# DasAltimeter_square_v0_1.net
KiCad netlist of a schematic drawn in EAGLE
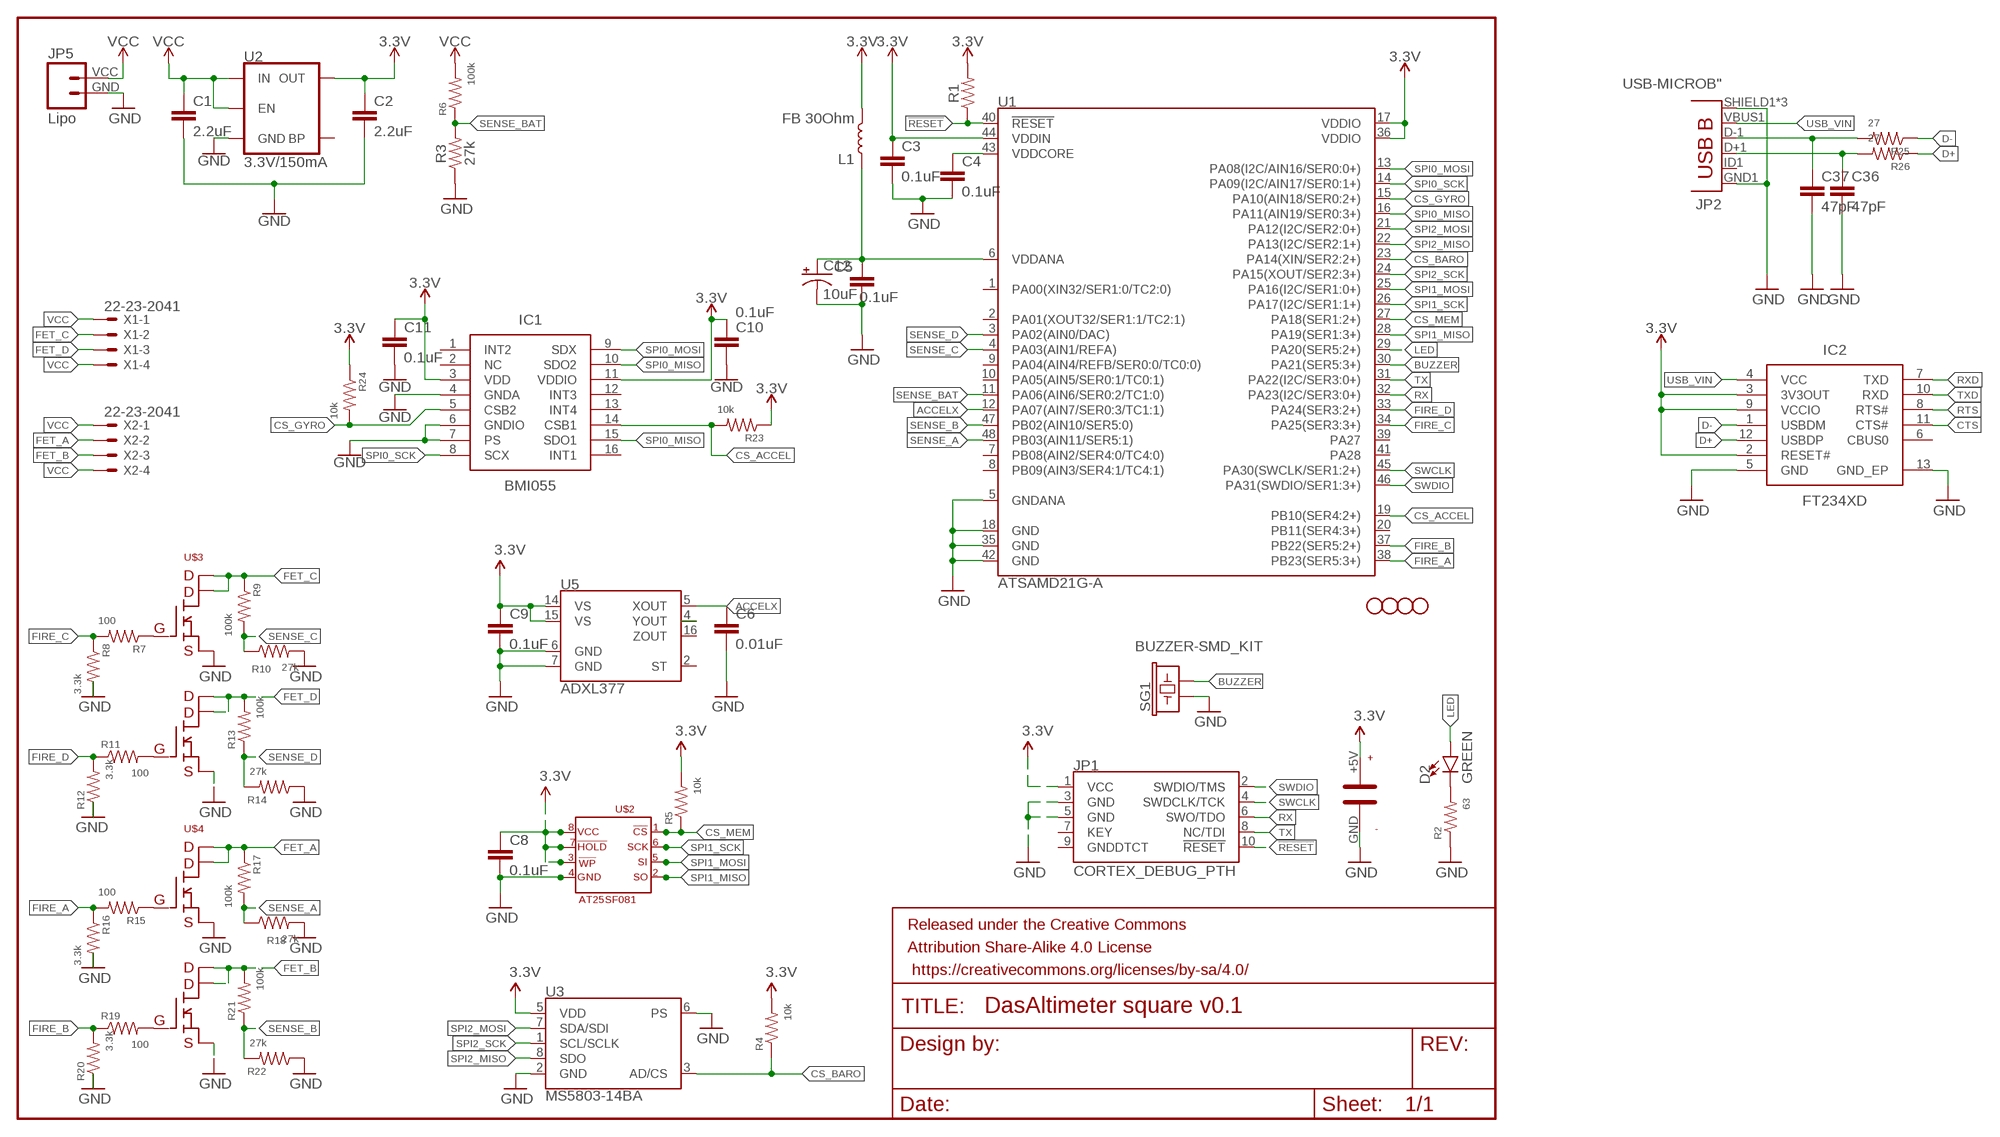
[diagram p0: schematic, sheet 1]

(export (version "E")
  (design (tool "Eeschema 10.0.6"))
  (components
    (comp (ref "C1")
      (value "2.2uF")
      (footprint "eagle-import:0603")
      (libsource (lib "eagle-import") (part "2.2UF-0603-10V-20%"))
    )
    (comp (ref "C2")
      (value "2.2uF")
      (footprint "eagle-import:0603")
      (libsource (lib "eagle-import") (part "2.2UF-0603-10V-20%"))
    )
    (comp (ref "C3")
      (value "0.1uF")
      (footprint "eagle-import:0402")
      (libsource (lib "eagle-import") (part "0.1UF-0402-16V-10%"))
    )
    (comp (ref "C4")
      (value "0.1uF")
      (footprint "eagle-import:0402")
      (libsource (lib "eagle-import") (part "0.1UF-0402-16V-10%"))
    )
    (comp (ref "C5")
      (value "0.1uF")
      (footprint "eagle-import:0402")
      (libsource (lib "eagle-import") (part "0.1UF-0402-16V-10%"))
    )
    (comp (ref "C6")
      (value "0.01uF")
      (footprint "eagle-import:0402")
      (libsource (lib "eagle-import") (part "0.1UF-0402-16V-10%"))
    )
    (comp (ref "C8")
      (value "0.1uF")
      (footprint "eagle-import:0402")
      (libsource (lib "eagle-import") (part "0.1UF-0402-16V-10%"))
    )
    (comp (ref "C9")
      (value "0.1uF")
      (footprint "eagle-import:0402")
      (libsource (lib "eagle-import") (part "0.1UF-0402-16V-10%"))
    )
    (comp (ref "C10")
      (value "0.1uF")
      (footprint "eagle-import:0402")
      (libsource (lib "eagle-import") (part "0.1UF-0402-16V-10%"))
    )
    (comp (ref "C11")
      (value "0.1uF")
      (footprint "eagle-import:0402")
      (libsource (lib "eagle-import") (part "0.1UF-0402-16V-10%"))
    )
    (comp (ref "C12")
      (value "10uF")
      (footprint "eagle-import:0603-POLAR")
      (libsource (lib "eagle-import") (part "10UF-POLAR-0603-6.3V-20%(TANT)"))
    )
    (comp (ref "C36")
      (value "47pF")
      (footprint "eagle-import:0402")
      (libsource (lib "eagle-import") (part "0.1UF-0402-16V-10%"))
    )
    (comp (ref "C37")
      (value "47pF")
      (footprint "eagle-import:0402")
      (libsource (lib "eagle-import") (part "0.1UF-0402-16V-10%"))
    )
    (comp (ref "D2")
      (value "GREEN")
      (footprint "eagle-import:LED-1206")
      (libsource (lib "eagle-import") (part "LED-GREEN1206"))
    )
    (comp (ref "FRAME1")
      (value "FRAME-LETTERNO_PACKAGE")
      (footprint "eagle-import:DUMMY")
      (fields (field (name "DESIGNER") "Nobody"))
      (libsource (lib "eagle-import") (part "FRAME-LETTERNO_PACKAGE"))
    )
    (comp (ref "H1")
      (value "STAND-OFFTIGHT")
      (footprint "eagle-import:STAND-OFF-TIGHT")
      (libsource (lib "eagle-import") (part "STAND-OFFTIGHT"))
    )
    (comp (ref "H2")
      (value "STAND-OFFTIGHT")
      (footprint "eagle-import:STAND-OFF-TIGHT")
      (libsource (lib "eagle-import") (part "STAND-OFFTIGHT"))
    )
    (comp (ref "H3")
      (value "STAND-OFFTIGHT")
      (footprint "eagle-import:STAND-OFF-TIGHT")
      (libsource (lib "eagle-import") (part "STAND-OFFTIGHT"))
    )
    (comp (ref "H4")
      (value "STAND-OFFTIGHT")
      (footprint "eagle-import:STAND-OFF-TIGHT")
      (libsource (lib "eagle-import") (part "STAND-OFFTIGHT"))
    )
    (comp (ref "IC1")
      (value "BMI055")
      (footprint "eagle-import:BMI055")
      (libsource (lib "eagle-import") (part "BMI055"))
    )
    (comp (ref "IC2")
      (value "FT234XD")
      (footprint "eagle-import:SON45P300X300X80-13N")
      (fields (field (name "MANUFACTURER_PART_NUMBER") "ft234xd"))
      (libsource (lib "eagle-import") (part "FT234XD"))
    )
    (comp (ref "JP1")
      (value "CORTEX_DEBUG_PTH")
      (footprint "eagle-import:2X5-PTH-1.27MM")
      (libsource (lib "eagle-import") (part "CORTEX_DEBUG_PTH"))
    )
    (comp (ref "JP2")
      (value "USB-MICROB\"")
      (footprint "eagle-import:USB-B-MICRO-SMD_V03")
      (libsource (lib "eagle-import") (part "USB-MICROB{dblquote}"))
    )
    (comp (ref "JP5")
      (value "Lipo")
      (footprint "eagle-import:JST-2-SMD-VERT")
      (libsource (lib "eagle-import") (part "M024UCON-15767"))
    )
    (comp (ref "L1")
      (value "FB 30Ohm")
      (footprint "eagle-import:0603")
      (libsource (lib "eagle-import") (part "INDUCTOR-0603-33NH"))
    )
    (comp (ref "R1")
      (value "RESISTOR0402")
      (footprint "eagle-import:0402")
      (libsource (lib "eagle-import") (part "RESISTOR0402"))
    )
    (comp (ref "R2")
      (value "63")
      (footprint "eagle-import:0402")
      (libsource (lib "eagle-import") (part "RESISTOR0402"))
    )
    (comp (ref "R3")
      (value "27k")
      (footprint "eagle-import:0402")
      (libsource (lib "eagle-import") (part "RESISTOR0402"))
    )
    (comp (ref "R4")
      (value "10k")
      (footprint "eagle-import:0402")
      (libsource (lib "eagle-import") (part "RESISTOR0402"))
    )
    (comp (ref "R5")
      (value "10k")
      (footprint "eagle-import:0402")
      (libsource (lib "eagle-import") (part "RESISTOR0402"))
    )
    (comp (ref "R6")
      (value "100k")
      (footprint "eagle-import:0402")
      (libsource (lib "eagle-import") (part "RESISTOR0402"))
    )
    (comp (ref "R7")
      (value "100")
      (footprint "eagle-import:0402")
      (libsource (lib "eagle-import") (part "RESISTOR0402"))
    )
    (comp (ref "R8")
      (value "3.3k")
      (footprint "eagle-import:0402")
      (libsource (lib "eagle-import") (part "RESISTOR0402"))
    )
    (comp (ref "R9")
      (value "100k")
      (footprint "eagle-import:0402")
      (libsource (lib "eagle-import") (part "RESISTOR0402"))
    )
    (comp (ref "R10")
      (value "27k")
      (footprint "eagle-import:0402")
      (libsource (lib "eagle-import") (part "RESISTOR0402"))
    )
    (comp (ref "R11")
      (value "100")
      (footprint "eagle-import:0402")
      (libsource (lib "eagle-import") (part "RESISTOR0402"))
    )
    (comp (ref "R12")
      (value "3.3k")
      (footprint "eagle-import:0402")
      (libsource (lib "eagle-import") (part "RESISTOR0402"))
    )
    (comp (ref "R13")
      (value "100k")
      (footprint "eagle-import:0402")
      (libsource (lib "eagle-import") (part "RESISTOR0402"))
    )
    (comp (ref "R14")
      (value "27k")
      (footprint "eagle-import:0402")
      (libsource (lib "eagle-import") (part "RESISTOR0402"))
    )
    (comp (ref "R15")
      (value "100")
      (footprint "eagle-import:0402")
      (libsource (lib "eagle-import") (part "RESISTOR0402"))
    )
    (comp (ref "R16")
      (value "3.3k")
      (footprint "eagle-import:0402")
      (libsource (lib "eagle-import") (part "RESISTOR0402"))
    )
    (comp (ref "R17")
      (value "100k")
      (footprint "eagle-import:0402")
      (libsource (lib "eagle-import") (part "RESISTOR0402"))
    )
    (comp (ref "R18")
      (value "27k")
      (footprint "eagle-import:0402")
      (libsource (lib "eagle-import") (part "RESISTOR0402"))
    )
    (comp (ref "R19")
      (value "100")
      (footprint "eagle-import:0402")
      (libsource (lib "eagle-import") (part "RESISTOR0402"))
    )
    (comp (ref "R20")
      (value "3.3k")
      (footprint "eagle-import:0402")
      (libsource (lib "eagle-import") (part "RESISTOR0402"))
    )
    (comp (ref "R21")
      (value "100k")
      (footprint "eagle-import:0402")
      (libsource (lib "eagle-import") (part "RESISTOR0402"))
    )
    (comp (ref "R22")
      (value "27k")
      (footprint "eagle-import:0402")
      (libsource (lib "eagle-import") (part "RESISTOR0402"))
    )
    (comp (ref "R23")
      (value "10k")
      (footprint "eagle-import:0402")
      (libsource (lib "eagle-import") (part "RESISTOR0402"))
    )
    (comp (ref "R24")
      (value "10k")
      (footprint "eagle-import:0402")
      (libsource (lib "eagle-import") (part "RESISTOR0402"))
    )
    (comp (ref "R25")
      (value "27")
      (footprint "eagle-import:0402")
      (libsource (lib "eagle-import") (part "RESISTOR0402"))
    )
    (comp (ref "R26")
      (value "27")
      (footprint "eagle-import:0402")
      (libsource (lib "eagle-import") (part "RESISTOR0402"))
    )
    (comp (ref "SG1")
      (value "BUZZER-SMD_KIT")
      (footprint "eagle-import:BUZZER-CCV-KIT")
      (libsource (lib "eagle-import") (part "BUZZER-SMD_KIT"))
    )
    (comp (ref "U$1")
      (value "PB-5R0H104-R")
      (footprint "eagle-import:PB-5R0H104-R")
      (libsource (lib "eagle-import") (part "PB-5R0H104-R"))
    )
    (comp (ref "U$2")
      (value "AT25SF081")
      (footprint "eagle-import:AT25SF081")
      (libsource (lib "eagle-import") (part "AT25SF081"))
    )
    (comp (ref "U$3")
      (value "SI7232DN")
      (footprint "eagle-import:SI7232DN")
      (libsource (lib "eagle-import") (part "SI7232DN"))
    )
    (comp (ref "U$4")
      (value "SI7232DN")
      (footprint "eagle-import:SI7232DN")
      (libsource (lib "eagle-import") (part "SI7232DN"))
    )
    (comp (ref "U1")
      (value "ATSAMD21G-A")
      (footprint "eagle-import:TQFP-48")
      (libsource (lib "eagle-import") (part "ATSAMD21G-A"))
    )
    (comp (ref "U2")
      (value "3.3V/150mA")
      (footprint "eagle-import:SOT23-5")
      (libsource (lib "eagle-import") (part "V_REG_MIC52053.3V"))
    )
    (comp (ref "U3")
      (value "MS5803-14BA")
      (footprint "eagle-import:MS5803")
      (libsource (lib "eagle-import") (part "MS5803-14BA"))
    )
    (comp (ref "U5")
      (value "ADXL377")
      (footprint "eagle-import:LFCSP-16-3X3")
      (libsource (lib "eagle-import") (part "ADXL377"))
    )
    (comp (ref "X1")
      (value "22-23-2041")
      (footprint "eagle-import:22-23-2041")
      (fields (field (name "MF") "MOLEX"))
      (libsource (lib "eagle-import") (part "22-23-2041"))
    )
    (comp (ref "X2")
      (value "22-23-2041")
      (footprint "eagle-import:22-23-2041")
      (fields (field (name "MF") "MOLEX"))
      (libsource (lib "eagle-import") (part "22-23-2041"))
    )
  )
  (nets
    (net (code "1") (name "/~{RESET}") (class "Default")
      (node (ref "JP1") (pin "10") (pinfunction "~{RESET}_10") (pintype "bidirectional"))
      (node (ref "R1") (pin "1") (pinfunction "1_1") (pintype "passive"))
      (node (ref "U1") (pin "40") (pinfunction "~{RESET}_40") (pintype "bidirectional"))
    )
    (net (code "2") (name "3.3V") (class "Default")
      (node (ref "C10") (pin "1") (pinfunction "1_1") (pintype "passive"))
      (node (ref "C11") (pin "1") (pinfunction "1_1") (pintype "passive"))
      (node (ref "C2") (pin "1") (pinfunction "1_1") (pintype "passive"))
      (node (ref "C3") (pin "1") (pinfunction "1_1") (pintype "passive"))
      (node (ref "C8") (pin "1") (pinfunction "1_1") (pintype "passive"))
      (node (ref "C9") (pin "1") (pinfunction "1_1") (pintype "passive"))
      (node (ref "IC1") (pin "11") (pinfunction "VDDIO_11") (pintype "passive"))
      (node (ref "IC1") (pin "3") (pinfunction "VDD_3") (pintype "passive"))
      (node (ref "IC2") (pin "2") (pinfunction "RESET#_2") (pintype "passive"))
      (node (ref "IC2") (pin "3") (pinfunction "3V3OUT_3") (pintype "output"))
      (node (ref "IC2") (pin "9") (pinfunction "VCCIO_9") (pintype "power_in"))
      (node (ref "JP1") (pin "1") (pinfunction "VCC_1") (pintype "bidirectional"))
      (node (ref "L1") (pin "2") (pinfunction "2_2") (pintype "passive"))
      (node (ref "R1") (pin "2") (pinfunction "2_2") (pintype "passive"))
      (node (ref "R23") (pin "1") (pinfunction "1_1") (pintype "passive"))
      (node (ref "R24") (pin "1") (pinfunction "1_1") (pintype "passive"))
      (node (ref "R4") (pin "2") (pinfunction "2_2") (pintype "passive"))
      (node (ref "R5") (pin "2") (pinfunction "2_2") (pintype "passive"))
      (node (ref "U$1") (pin "+5V") (pinfunction "+5V_+5V") (pintype "bidirectional"))
      (node (ref "U$2") (pin "!HOLD") (pinfunction "~{HOLD}_!HOLD") (pintype "bidirectional"))
      (node (ref "U$2") (pin "!WP") (pinfunction "~{WP}_!WP") (pintype "bidirectional"))
      (node (ref "U$2") (pin "VCC") (pinfunction "VCC_VCC") (pintype "bidirectional"))
      (node (ref "U1") (pin "17") (pinfunction "VDDIO_17") (pintype "bidirectional"))
      (node (ref "U1") (pin "36") (pinfunction "VDDIO_36") (pintype "bidirectional"))
      (node (ref "U1") (pin "44") (pinfunction "VDDIN_44") (pintype "bidirectional"))
      (node (ref "U2") (pin "5") (pinfunction "OUT_5") (pintype "passive"))
      (node (ref "U3") (pin "5") (pinfunction "VDD_5") (pintype "bidirectional"))
      (node (ref "U5") (pin "14") (pinfunction "VS_14") (pintype "bidirectional"))
      (node (ref "U5") (pin "15") (pinfunction "VS_15") (pintype "bidirectional"))
    )
    (net (code "3") (name "ACCELX") (class "Default")
      (node (ref "C6") (pin "1") (pinfunction "1_1") (pintype "passive"))
      (node (ref "U1") (pin "12") (pinfunction "PA07(AIN7/SER0:3/TC1:1)_12") (pintype "bidirectional"))
      (node (ref "U5") (pin "5") (pinfunction "XOUT_5") (pintype "bidirectional"))
    )
    (net (code "4") (name "BUZZER") (class "Default")
      (node (ref "SG1") (pin "-") (pinfunction "2_-") (pintype "passive"))
      (node (ref "U1") (pin "30") (pinfunction "PA21(SER5:3+)_30") (pintype "bidirectional"))
    )
    (net (code "5") (name "CS_ACCEL") (class "Default")
      (node (ref "IC1") (pin "14") (pinfunction "CSB1_14") (pintype "passive"))
      (node (ref "R23") (pin "2") (pinfunction "2_2") (pintype "passive"))
      (node (ref "U1") (pin "19") (pinfunction "PB10(SER4:2+)_19") (pintype "bidirectional"))
    )
    (net (code "6") (name "CS_BARO") (class "Default")
      (node (ref "R4") (pin "1") (pinfunction "1_1") (pintype "passive"))
      (node (ref "U1") (pin "23") (pinfunction "PA14(XIN/SER2:2+)_23") (pintype "bidirectional"))
      (node (ref "U3") (pin "3") (pinfunction "AD/CS_3") (pintype "bidirectional"))
    )
    (net (code "7") (name "CS_GYRO") (class "Default")
      (node (ref "IC1") (pin "5") (pinfunction "CSB2_5") (pintype "passive"))
      (node (ref "R24") (pin "2") (pinfunction "2_2") (pintype "passive"))
      (node (ref "U1") (pin "15") (pinfunction "PA10(AIN18/SER0:2+)_15") (pintype "bidirectional"))
    )
    (net (code "8") (name "CS_MEM") (class "Default")
      (node (ref "R5") (pin "1") (pinfunction "1_1") (pintype "passive"))
      (node (ref "U$2") (pin "!CS") (pinfunction "~{CS}_!CS") (pintype "bidirectional"))
      (node (ref "U1") (pin "27") (pinfunction "PA18(SER1:2+)_27") (pintype "bidirectional"))
    )
    (net (code "9") (name "CTS") (class "Default")
      (node (ref "IC2") (pin "11") (pinfunction "CTS#_11") (pintype "passive"))
    )
    (net (code "10") (name "D+") (class "Default")
      (node (ref "IC2") (pin "12") (pinfunction "USBDP_12") (pintype "passive"))
      (node (ref "R26") (pin "1") (pinfunction "1_1") (pintype "passive"))
    )
    (net (code "11") (name "D-") (class "Default")
      (node (ref "IC2") (pin "1") (pinfunction "USBDM_1") (pintype "passive"))
      (node (ref "R25") (pin "1") (pinfunction "1_1") (pintype "passive"))
    )
    (net (code "12") (name "FET_A") (class "Default")
      (node (ref "R17") (pin "1") (pinfunction "1_1") (pintype "passive"))
      (node (ref "U$4") (pin "7") (pinfunction "PIN7_7") (pintype "bidirectional"))
      (node (ref "U$4") (pin "8") (pinfunction "PIN8_8") (pintype "bidirectional"))
      (node (ref "U$4") (pin "9") (pinfunction "PIN8_9") (pintype "bidirectional"))
      (node (ref "X2") (pin "2") (pinfunction "S_2") (pintype "passive"))
    )
    (net (code "13") (name "FET_B") (class "Default")
      (node (ref "R21") (pin "2") (pinfunction "2_2") (pintype "passive"))
      (node (ref "U$4") (pin "10") (pinfunction "PIN5_10") (pintype "bidirectional"))
      (node (ref "U$4") (pin "5") (pinfunction "PIN5_5") (pintype "bidirectional"))
      (node (ref "U$4") (pin "6") (pinfunction "PIN6_6") (pintype "bidirectional"))
      (node (ref "X2") (pin "3") (pinfunction "S_3") (pintype "passive"))
    )
    (net (code "14") (name "FET_C") (class "Default")
      (node (ref "R9") (pin "1") (pinfunction "1_1") (pintype "passive"))
      (node (ref "U$3") (pin "7") (pinfunction "PIN7_7") (pintype "bidirectional"))
      (node (ref "U$3") (pin "8") (pinfunction "PIN8_8") (pintype "bidirectional"))
      (node (ref "U$3") (pin "9") (pinfunction "PIN8_9") (pintype "bidirectional"))
      (node (ref "X1") (pin "2") (pinfunction "S_2") (pintype "passive"))
    )
    (net (code "15") (name "FET_D") (class "Default")
      (node (ref "R13") (pin "2") (pinfunction "2_2") (pintype "passive"))
      (node (ref "U$3") (pin "10") (pinfunction "PIN5_10") (pintype "bidirectional"))
      (node (ref "U$3") (pin "5") (pinfunction "PIN5_5") (pintype "bidirectional"))
      (node (ref "U$3") (pin "6") (pinfunction "PIN6_6") (pintype "bidirectional"))
      (node (ref "X1") (pin "3") (pinfunction "S_3") (pintype "passive"))
    )
    (net (code "16") (name "FIRE_A") (class "Default")
      (node (ref "R15") (pin "2") (pinfunction "2_2") (pintype "passive"))
      (node (ref "R16") (pin "1") (pinfunction "1_1") (pintype "passive"))
      (node (ref "U1") (pin "38") (pinfunction "PB23(SER5:3+)_38") (pintype "bidirectional"))
    )
    (net (code "17") (name "FIRE_B") (class "Default")
      (node (ref "R19") (pin "1") (pinfunction "1_1") (pintype "passive"))
      (node (ref "R20") (pin "2") (pinfunction "2_2") (pintype "passive"))
      (node (ref "U1") (pin "37") (pinfunction "PB22(SER5:2+)_37") (pintype "bidirectional"))
    )
    (net (code "18") (name "FIRE_C") (class "Default")
      (node (ref "R7") (pin "2") (pinfunction "2_2") (pintype "passive"))
      (node (ref "R8") (pin "1") (pinfunction "1_1") (pintype "passive"))
      (node (ref "U1") (pin "34") (pinfunction "PA25(SER3:3+)_34") (pintype "bidirectional"))
    )
    (net (code "19") (name "FIRE_D") (class "Default")
      (node (ref "R11") (pin "1") (pinfunction "1_1") (pintype "passive"))
      (node (ref "R12") (pin "2") (pinfunction "2_2") (pintype "passive"))
      (node (ref "U1") (pin "33") (pinfunction "PA24(SER3:2+)_33") (pintype "bidirectional"))
    )
    (net (code "20") (name "GND") (class "Default")
      (node (ref "C1") (pin "2") (pinfunction "2_2") (pintype "passive"))
      (node (ref "C10") (pin "2") (pinfunction "2_2") (pintype "passive"))
      (node (ref "C11") (pin "2") (pinfunction "2_2") (pintype "passive"))
      (node (ref "C12") (pin "-") (pinfunction "-_-") (pintype "passive"))
      (node (ref "C2") (pin "2") (pinfunction "2_2") (pintype "passive"))
      (node (ref "C3") (pin "2") (pinfunction "2_2") (pintype "passive"))
      (node (ref "C36") (pin "2") (pinfunction "2_2") (pintype "passive"))
      (node (ref "C37") (pin "2") (pinfunction "2_2") (pintype "passive"))
      (node (ref "C4") (pin "2") (pinfunction "2_2") (pintype "passive"))
      (node (ref "C5") (pin "2") (pinfunction "2_2") (pintype "passive"))
      (node (ref "C6") (pin "2") (pinfunction "2_2") (pintype "passive"))
      (node (ref "C8") (pin "2") (pinfunction "2_2") (pintype "passive"))
      (node (ref "C9") (pin "2") (pinfunction "2_2") (pintype "passive"))
      (node (ref "IC1") (pin "4") (pinfunction "GNDA_4") (pintype "passive"))
      (node (ref "IC1") (pin "6") (pinfunction "GNDIO_6") (pintype "passive"))
      (node (ref "IC1") (pin "7") (pinfunction "PS_7") (pintype "passive"))
      (node (ref "IC2") (pin "13") (pinfunction "GND_EP_13") (pintype "power_in"))
      (node (ref "IC2") (pin "5") (pinfunction "GND_5") (pintype "power_in"))
      (node (ref "JP1") (pin "3") (pinfunction "GND_3") (pintype "bidirectional"))
      (node (ref "JP1") (pin "5") (pinfunction "GND_5") (pintype "bidirectional"))
      (node (ref "JP2") (pin "GND1") (pinfunction "GND_GND1") (pintype "bidirectional"))
      (node (ref "JP2") (pin "SHIELD1") (pinfunction "SHIELD_SHIELD1") (pintype "bidirectional"))
      (node (ref "JP2") (pin "SHIELD2") (pinfunction "SHIELD_SHIELD2") (pintype "bidirectional"))
      (node (ref "JP2") (pin "SHIELD3") (pinfunction "SHIELD_SHIELD3") (pintype "bidirectional"))
      (node (ref "JP5") (pin "GND") (pinfunction "1_GND") (pintype "passive"))
      (node (ref "R10") (pin "2") (pinfunction "2_2") (pintype "passive"))
      (node (ref "R12") (pin "1") (pinfunction "1_1") (pintype "passive"))
      (node (ref "R14") (pin "1") (pinfunction "1_1") (pintype "passive"))
      (node (ref "R16") (pin "2") (pinfunction "2_2") (pintype "passive"))
      (node (ref "R18") (pin "2") (pinfunction "2_2") (pintype "passive"))
      (node (ref "R2") (pin "1") (pinfunction "1_1") (pintype "passive"))
      (node (ref "R20") (pin "1") (pinfunction "1_1") (pintype "passive"))
      (node (ref "R22") (pin "1") (pinfunction "1_1") (pintype "passive"))
      (node (ref "R3") (pin "1") (pinfunction "1_1") (pintype "passive"))
      (node (ref "R8") (pin "2") (pinfunction "2_2") (pintype "passive"))
      (node (ref "SG1") (pin "+") (pinfunction "1_+") (pintype "passive"))
      (node (ref "U$1") (pin "GND") (pinfunction "GND_GND") (pintype "bidirectional"))
      (node (ref "U$2") (pin "GND") (pinfunction "GND_GND") (pintype "bidirectional"))
      (node (ref "U$3") (pin "1") (pinfunction "PIN1_1") (pintype "bidirectional"))
      (node (ref "U$3") (pin "3") (pinfunction "PIN3_3") (pintype "bidirectional"))
      (node (ref "U$4") (pin "1") (pinfunction "PIN1_1") (pintype "bidirectional"))
      (node (ref "U$4") (pin "3") (pinfunction "PIN3_3") (pintype "bidirectional"))
      (node (ref "U1") (pin "18") (pinfunction "GND_18") (pintype "bidirectional"))
      (node (ref "U1") (pin "35") (pinfunction "GND_35") (pintype "bidirectional"))
      (node (ref "U1") (pin "42") (pinfunction "GND_42") (pintype "bidirectional"))
      (node (ref "U1") (pin "5") (pinfunction "GNDANA_5") (pintype "bidirectional"))
      (node (ref "U2") (pin "2") (pinfunction "GND_2") (pintype "input"))
      (node (ref "U3") (pin "2") (pinfunction "GND_2") (pintype "bidirectional"))
      (node (ref "U3") (pin "6") (pinfunction "PS_6") (pintype "bidirectional"))
      (node (ref "U5") (pin "6") (pinfunction "GND_6") (pintype "bidirectional"))
      (node (ref "U5") (pin "7") (pinfunction "GND_7") (pintype "bidirectional"))
    )
    (net (code "21") (name "LED") (class "Default")
      (node (ref "D2") (pin "A") (pinfunction "A_A") (pintype "passive"))
      (node (ref "U1") (pin "29") (pinfunction "PA20(SER5:2+)_29") (pintype "bidirectional"))
    )
    (net (code "22") (name "Net-(D2-PadC)") (class "Default")
      (node (ref "D2") (pin "C") (pinfunction "C_C") (pintype "passive"))
      (node (ref "R2") (pin "2") (pinfunction "2_2") (pintype "passive"))
    )
    (net (code "23") (name "Net-(JP2-D+)") (class "Default")
      (node (ref "C36") (pin "1") (pinfunction "1_1") (pintype "passive"))
      (node (ref "JP2") (pin "D+1") (pinfunction "D+_D+1") (pintype "bidirectional"))
      (node (ref "R26") (pin "2") (pinfunction "2_2") (pintype "passive"))
    )
    (net (code "24") (name "Net-(JP2-D-)") (class "Default")
      (node (ref "C37") (pin "1") (pinfunction "1_1") (pintype "passive"))
      (node (ref "JP2") (pin "D-1") (pinfunction "D-_D-1") (pintype "bidirectional"))
      (node (ref "R25") (pin "2") (pinfunction "2_2") (pintype "passive"))
    )
    (net (code "25") (name "Net-(U$3-PIN2)") (class "Default")
      (node (ref "R7") (pin "1") (pinfunction "1_1") (pintype "passive"))
      (node (ref "U$3") (pin "2") (pinfunction "PIN2_2") (pintype "bidirectional"))
    )
    (net (code "26") (name "Net-(U$3-PIN4)") (class "Default")
      (node (ref "R11") (pin "2") (pinfunction "2_2") (pintype "passive"))
      (node (ref "U$3") (pin "4") (pinfunction "PIN4_4") (pintype "bidirectional"))
    )
    (net (code "27") (name "Net-(U$4-PIN2)") (class "Default")
      (node (ref "R15") (pin "1") (pinfunction "1_1") (pintype "passive"))
      (node (ref "U$4") (pin "2") (pinfunction "PIN2_2") (pintype "bidirectional"))
    )
    (net (code "28") (name "Net-(U$4-PIN4)") (class "Default")
      (node (ref "R19") (pin "2") (pinfunction "2_2") (pintype "passive"))
      (node (ref "U$4") (pin "4") (pinfunction "PIN4_4") (pintype "bidirectional"))
    )
    (net (code "29") (name "Net-(U1-VDDANA)") (class "Default")
      (node (ref "C12") (pin "+") (pinfunction "+_+") (pintype "passive"))
      (node (ref "C5") (pin "1") (pinfunction "1_1") (pintype "passive"))
      (node (ref "L1") (pin "1") (pinfunction "1_1") (pintype "passive"))
      (node (ref "U1") (pin "6") (pinfunction "VDDANA_6") (pintype "bidirectional"))
    )
    (net (code "30") (name "Net-(U1-VDDCORE)") (class "Default")
      (node (ref "C4") (pin "1") (pinfunction "1_1") (pintype "passive"))
      (node (ref "U1") (pin "43") (pinfunction "VDDCORE_43") (pintype "bidirectional"))
    )
    (net (code "31") (name "RTS") (class "Default")
      (node (ref "IC2") (pin "8") (pinfunction "RTS#_8") (pintype "passive"))
    )
    (net (code "32") (name "RX") (class "Default")
      (node (ref "JP1") (pin "6") (pinfunction "SWO/TDO_6") (pintype "bidirectional"))
      (node (ref "U1") (pin "32") (pinfunction "PA23(I2C/SER3:0+)_32") (pintype "bidirectional"))
    )
    (net (code "33") (name "RXD") (class "Default")
      (node (ref "IC2") (pin "7") (pinfunction "TXD_7") (pintype "passive"))
    )
    (net (code "34") (name "SENSE_A") (class "Default")
      (node (ref "R17") (pin "2") (pinfunction "2_2") (pintype "passive"))
      (node (ref "R18") (pin "1") (pinfunction "1_1") (pintype "passive"))
      (node (ref "U1") (pin "48") (pinfunction "PB03(AIN11/SER5:1)_48") (pintype "bidirectional"))
    )
    (net (code "35") (name "SENSE_B") (class "Default")
      (node (ref "R21") (pin "1") (pinfunction "1_1") (pintype "passive"))
      (node (ref "R22") (pin "2") (pinfunction "2_2") (pintype "passive"))
      (node (ref "U1") (pin "47") (pinfunction "PB02(AIN10/SER5:0)_47") (pintype "bidirectional"))
    )
    (net (code "36") (name "SENSE_BAT") (class "Default")
      (node (ref "R3") (pin "2") (pinfunction "2_2") (pintype "passive"))
      (node (ref "R6") (pin "1") (pinfunction "1_1") (pintype "passive"))
      (node (ref "U1") (pin "11") (pinfunction "PA06(AIN6/SER0:2/TC1:0)_11") (pintype "bidirectional"))
    )
    (net (code "37") (name "SENSE_C") (class "Default")
      (node (ref "R10") (pin "1") (pinfunction "1_1") (pintype "passive"))
      (node (ref "R9") (pin "2") (pinfunction "2_2") (pintype "passive"))
      (node (ref "U1") (pin "4") (pinfunction "PA03(AIN1/REFA)_4") (pintype "bidirectional"))
    )
    (net (code "38") (name "SENSE_D") (class "Default")
      (node (ref "R13") (pin "1") (pinfunction "1_1") (pintype "passive"))
      (node (ref "R14") (pin "2") (pinfunction "2_2") (pintype "passive"))
      (node (ref "U1") (pin "3") (pinfunction "PA02(AIN0/DAC)_3") (pintype "bidirectional"))
    )
    (net (code "39") (name "SPI0_MISO") (class "Default")
      (node (ref "IC1") (pin "10") (pinfunction "SDO2_10") (pintype "passive"))
      (node (ref "IC1") (pin "15") (pinfunction "SDO1_15") (pintype "passive"))
      (node (ref "U1") (pin "16") (pinfunction "PA11(AIN19/SER0:3+)_16") (pintype "bidirectional"))
    )
    (net (code "40") (name "SPI0_MOSI") (class "Default")
      (node (ref "IC1") (pin "9") (pinfunction "SDX_9") (pintype "passive"))
      (node (ref "U1") (pin "13") (pinfunction "PA08(I2C/AIN16/SER0:0+)_13") (pintype "bidirectional"))
    )
    (net (code "41") (name "SPI0_SCK") (class "Default")
      (node (ref "IC1") (pin "8") (pinfunction "SCX_8") (pintype "passive"))
      (node (ref "U1") (pin "14") (pinfunction "PA09(I2C/AIN17/SER0:1+)_14") (pintype "bidirectional"))
    )
    (net (code "42") (name "SPI1_MISO") (class "Default")
      (node (ref "U$2") (pin "SO") (pinfunction "SO_SO") (pintype "bidirectional"))
      (node (ref "U1") (pin "28") (pinfunction "PA19(SER1:3+)_28") (pintype "bidirectional"))
    )
    (net (code "43") (name "SPI1_MOSI") (class "Default")
      (node (ref "U$2") (pin "SI") (pinfunction "SI_SI") (pintype "bidirectional"))
      (node (ref "U1") (pin "25") (pinfunction "PA16(I2C/SER1:0+)_25") (pintype "bidirectional"))
    )
    (net (code "44") (name "SPI1_SCK") (class "Default")
      (node (ref "U$2") (pin "SCK") (pinfunction "SCK_SCK") (pintype "bidirectional"))
      (node (ref "U1") (pin "26") (pinfunction "PA17(I2C/SER1:1+)_26") (pintype "bidirectional"))
    )
    (net (code "45") (name "SPI2_MISO") (class "Default")
      (node (ref "U1") (pin "22") (pinfunction "PA13(I2C/SER2:1+)_22") (pintype "bidirectional"))
      (node (ref "U3") (pin "8") (pinfunction "SDO_8") (pintype "bidirectional"))
    )
    (net (code "46") (name "SPI2_MOSI") (class "Default")
      (node (ref "U1") (pin "21") (pinfunction "PA12(I2C/SER2:0+)_21") (pintype "bidirectional"))
      (node (ref "U3") (pin "7") (pinfunction "SDA/SDI_7") (pintype "bidirectional"))
    )
    (net (code "47") (name "SPI2_SCK") (class "Default")
      (node (ref "U1") (pin "24") (pinfunction "PA15(XOUT/SER2:3+)_24") (pintype "bidirectional"))
      (node (ref "U3") (pin "1") (pinfunction "SCL/SCLK_1") (pintype "bidirectional"))
    )
    (net (code "48") (name "SWCLK") (class "Default")
      (node (ref "JP1") (pin "4") (pinfunction "SWDCLK/TCK_4") (pintype "bidirectional"))
      (node (ref "U1") (pin "45") (pinfunction "PA30(SWCLK/SER1:2+)_45") (pintype "bidirectional"))
    )
    (net (code "49") (name "SWDIO") (class "Default")
      (node (ref "JP1") (pin "2") (pinfunction "SWDIO/TMS_2") (pintype "bidirectional"))
      (node (ref "U1") (pin "46") (pinfunction "PA31(SWDIO/SER1:3+)_46") (pintype "bidirectional"))
    )
    (net (code "50") (name "TX") (class "Default")
      (node (ref "JP1") (pin "8") (pinfunction "NC/TDI_8") (pintype "bidirectional"))
      (node (ref "U1") (pin "31") (pinfunction "PA22(I2C/SER3:0+)_31") (pintype "bidirectional"))
    )
    (net (code "51") (name "TXD") (class "Default")
      (node (ref "IC2") (pin "10") (pinfunction "RXD_10") (pintype "passive"))
    )
    (net (code "52") (name "USB_VIN") (class "Default")
      (node (ref "IC2") (pin "4") (pinfunction "VCC_4") (pintype "power_in"))
      (node (ref "JP2") (pin "VBUS1") (pinfunction "VBUS_VBUS1") (pintype "bidirectional"))
    )
    (net (code "53") (name "VCC") (class "Default")
      (node (ref "C1") (pin "1") (pinfunction "1_1") (pintype "passive"))
      (node (ref "JP5") (pin "VCC") (pinfunction "2_VCC") (pintype "passive"))
      (node (ref "R6") (pin "2") (pinfunction "2_2") (pintype "passive"))
      (node (ref "U2") (pin "1") (pinfunction "IN_1") (pintype "input"))
      (node (ref "U2") (pin "3") (pinfunction "EN_3") (pintype "input"))
      (node (ref "X1") (pin "1") (pinfunction "S_1") (pintype "passive"))
      (node (ref "X1") (pin "4") (pinfunction "S_4") (pintype "passive"))
      (node (ref "X2") (pin "1") (pinfunction "S_1") (pintype "passive"))
      (node (ref "X2") (pin "4") (pinfunction "S_4") (pintype "passive"))
    )
    (net (code "54") (name "unconnected-(IC1-INT1-Pad16)") (class "Default")
      (node (ref "IC1") (pin "16") (pinfunction "INT1_16") (pintype "passive"))
    )
    (net (code "55") (name "unconnected-(IC1-INT2-Pad1)") (class "Default")
      (node (ref "IC1") (pin "1") (pinfunction "INT2_1") (pintype "passive"))
    )
    (net (code "56") (name "unconnected-(IC1-INT3-Pad12)") (class "Default")
      (node (ref "IC1") (pin "12") (pinfunction "INT3_12") (pintype "passive"))
    )
    (net (code "57") (name "unconnected-(IC1-INT4-Pad13)") (class "Default")
      (node (ref "IC1") (pin "13") (pinfunction "INT4_13") (pintype "passive"))
    )
    (net (code "58") (name "unconnected-(IC1-NC-Pad2)") (class "Default")
      (node (ref "IC1") (pin "2") (pinfunction "NC_2") (pintype "no_connect"))
    )
    (net (code "59") (name "unconnected-(IC2-CBUS0-Pad6)") (class "Default")
      (node (ref "IC2") (pin "6") (pinfunction "CBUS0_6") (pintype "passive"))
    )
    (net (code "60") (name "unconnected-(JP1-GNDDTCT-Pad9)") (class "Default")
      (node (ref "JP1") (pin "9") (pinfunction "GNDDTCT_9") (pintype "bidirectional"))
    )
    (net (code "61") (name "unconnected-(JP1-KEY-Pad7)") (class "Default")
      (node (ref "JP1") (pin "7") (pinfunction "KEY_7") (pintype "bidirectional"))
    )
    (net (code "62") (name "unconnected-(JP2-USBID-PadID1)") (class "Default")
      (node (ref "JP2") (pin "ID1") (pinfunction "USBID_ID1") (pintype "bidirectional"))
    )
    (net (code "63") (name "unconnected-(U1-PA00(XIN32{slash}SER1:0{slash}TC2:0)-Pad1)") (class "Default")
      (node (ref "U1") (pin "1") (pinfunction "PA00(XIN32/SER1:0/TC2:0)_1") (pintype "bidirectional"))
    )
    (net (code "64") (name "unconnected-(U1-PA01(XOUT32{slash}SER1:1{slash}TC2:1)-Pad2)") (class "Default")
      (node (ref "U1") (pin "2") (pinfunction "PA01(XOUT32/SER1:1/TC2:1)_2") (pintype "bidirectional"))
    )
    (net (code "65") (name "unconnected-(U1-PA04(AIN4{slash}REFB{slash}SER0:0{slash}TC0:0)-Pad9)") (class "Default")
      (node (ref "U1") (pin "9") (pinfunction "PA04(AIN4/REFB/SER0:0/TC0:0)_9") (pintype "bidirectional"))
    )
    (net (code "66") (name "unconnected-(U1-PA05(AIN5{slash}SER0:1{slash}TC0:1)-Pad10)") (class "Default")
      (node (ref "U1") (pin "10") (pinfunction "PA05(AIN5/SER0:1/TC0:1)_10") (pintype "bidirectional"))
    )
    (net (code "67") (name "unconnected-(U1-PA27-Pad39)") (class "Default")
      (node (ref "U1") (pin "39") (pinfunction "PA27_39") (pintype "bidirectional"))
    )
    (net (code "68") (name "unconnected-(U1-PA28-Pad41)") (class "Default")
      (node (ref "U1") (pin "41") (pinfunction "PA28_41") (pintype "bidirectional"))
    )
    (net (code "69") (name "unconnected-(U1-PB08(AIN2{slash}SER4:0{slash}TC4:0)-Pad7)") (class "Default")
      (node (ref "U1") (pin "7") (pinfunction "PB08(AIN2/SER4:0/TC4:0)_7") (pintype "bidirectional"))
    )
    (net (code "70") (name "unconnected-(U1-PB09(AIN3{slash}SER4:1{slash}TC4:1)-Pad8)") (class "Default")
      (node (ref "U1") (pin "8") (pinfunction "PB09(AIN3/SER4:1/TC4:1)_8") (pintype "bidirectional"))
    )
    (net (code "71") (name "unconnected-(U1-PB11(SER4:3+)-Pad20)") (class "Default")
      (node (ref "U1") (pin "20") (pinfunction "PB11(SER4:3+)_20") (pintype "bidirectional"))
    )
    (net (code "72") (name "unconnected-(U2-BP-Pad4)") (class "Default")
      (node (ref "U2") (pin "4") (pinfunction "BP_4") (pintype "input"))
    )
    (net (code "73") (name "unconnected-(U5-ST-Pad2)") (class "Default")
      (node (ref "U5") (pin "2") (pinfunction "ST_2") (pintype "bidirectional"))
    )
    (net (code "74") (name "unconnected-(U5-YOUT-Pad4)") (class "Default")
      (node (ref "U5") (pin "4") (pinfunction "YOUT_4") (pintype "bidirectional"))
    )
    (net (code "75") (name "unconnected-(U5-ZOUT-Pad16)") (class "Default")
      (node (ref "U5") (pin "16") (pinfunction "ZOUT_16") (pintype "bidirectional"))
    )
  )
)
